# control-cluster-test.net
KiCad netlist of a schematic drawn in Altium Designer
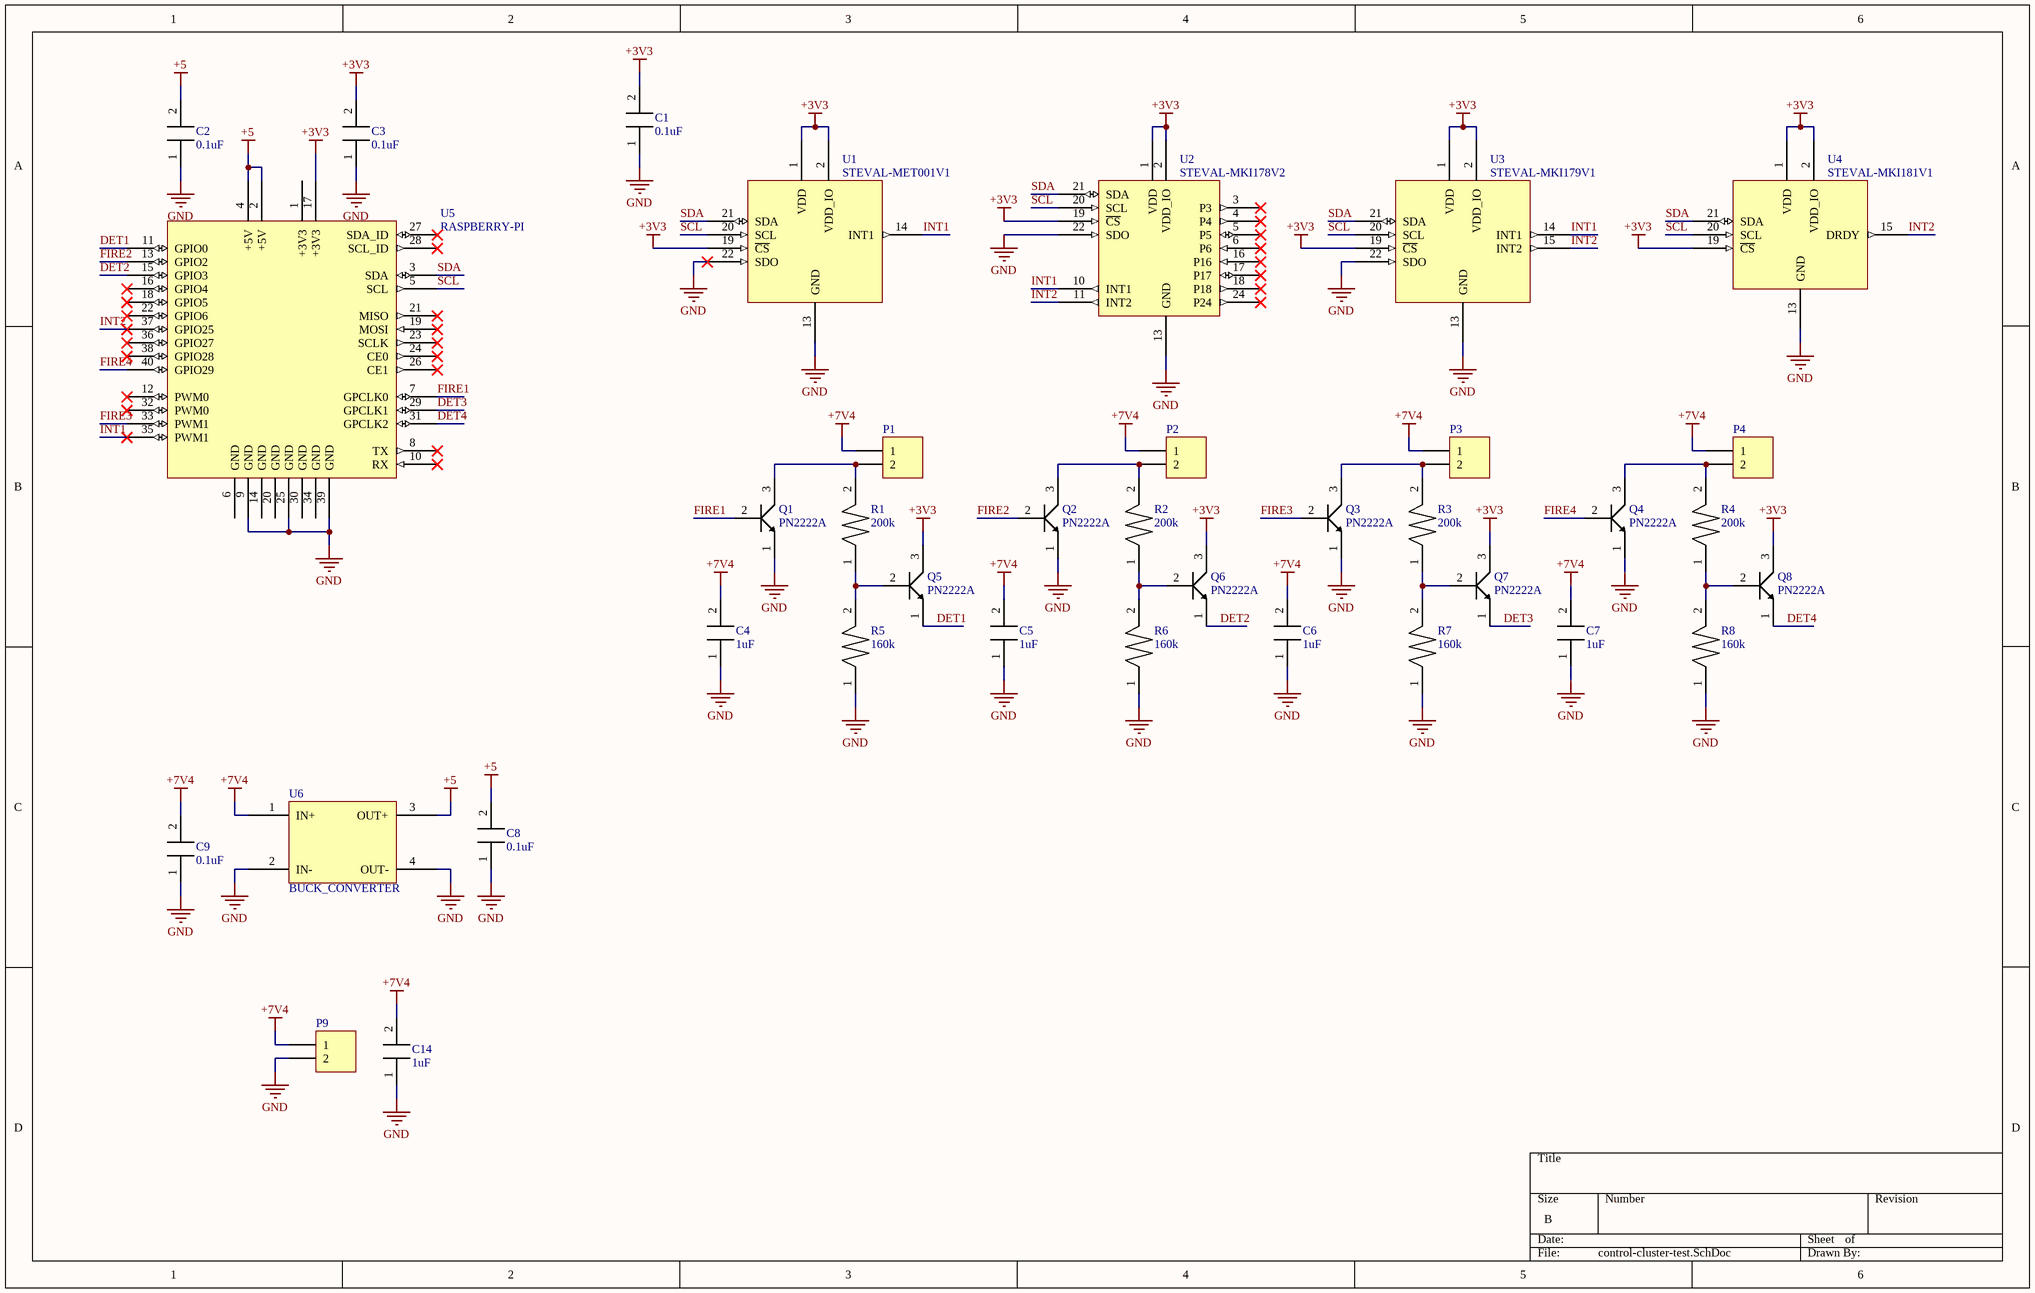
[diagram p0: control-cluster-test.SchDoc]

(export (version "E")
  (design (tool "Eeschema 10.0.6"))
  (components
    (comp (ref "C1")
      (value "0.1uF")
      (footprint "CAPACITOR")
      (libsource (lib "control-cluster-test") (part "CAPACITOR"))
    )
    (comp (ref "C2")
      (value "0.1uF")
      (footprint "CAPACITOR")
      (libsource (lib "control-cluster-test") (part "CAPACITOR"))
    )
    (comp (ref "C3")
      (value "0.1uF")
      (footprint "CAPACITOR")
      (libsource (lib "control-cluster-test") (part "CAPACITOR"))
    )
    (comp (ref "C4")
      (value "1uF")
      (footprint "CAPACITOR")
      (libsource (lib "control-cluster-test") (part "CAPACITOR"))
    )
    (comp (ref "C5")
      (value "1uF")
      (footprint "CAPACITOR")
      (libsource (lib "control-cluster-test") (part "CAPACITOR"))
    )
    (comp (ref "C6")
      (value "1uF")
      (footprint "CAPACITOR")
      (libsource (lib "control-cluster-test") (part "CAPACITOR"))
    )
    (comp (ref "C7")
      (value "1uF")
      (footprint "CAPACITOR")
      (libsource (lib "control-cluster-test") (part "CAPACITOR"))
    )
    (comp (ref "C8")
      (value "0.1uF")
      (footprint "CAPACITOR")
      (libsource (lib "control-cluster-test") (part "CAPACITOR"))
    )
    (comp (ref "C9")
      (value "0.1uF")
      (footprint "CAPACITOR")
      (libsource (lib "control-cluster-test") (part "CAPACITOR"))
    )
    (comp (ref "C14")
      (value "1uF")
      (footprint "CAPACITOR")
      (libsource (lib "control-cluster-test") (part "CAPACITOR"))
    )
    (comp (ref "P1")
      (value "Header 2")
      (footprint "HDR1X2")
      (description "Header, 2-Pin")
      (fields (field (name "PUBLISHER") "Altium Limited"))
      (libsource (lib "Miscellaneous Connectors") (part "Header 2"))
    )
    (comp (ref "P2")
      (value "Header 2")
      (footprint "HDR1X2")
      (description "Header, 2-Pin")
      (fields (field (name "PUBLISHER") "Altium Limited"))
      (libsource (lib "Miscellaneous Connectors") (part "Header 2"))
    )
    (comp (ref "P3")
      (value "Header 2")
      (footprint "HDR1X2")
      (description "Header, 2-Pin")
      (fields (field (name "PUBLISHER") "Altium Limited"))
      (libsource (lib "Miscellaneous Connectors") (part "Header 2"))
    )
    (comp (ref "P4")
      (value "Header 2")
      (footprint "HDR1X2")
      (description "Header, 2-Pin")
      (fields (field (name "PUBLISHER") "Altium Limited"))
      (libsource (lib "Miscellaneous Connectors") (part "Header 2"))
    )
    (comp (ref "P9")
      (value "Header 2")
      (footprint "HDR1X2")
      (description "Header, 2-Pin")
      (fields (field (name "PUBLISHER") "Altium Limited"))
      (libsource (lib "Miscellaneous Connectors") (part "Header 2"))
    )
    (comp (ref "Q1")
      (value "PN2222A")
      (footprint "PN2222A")
      (libsource (lib "control-cluster-test") (part "PN2222A"))
    )
    (comp (ref "Q2")
      (value "PN2222A")
      (footprint "PN2222A")
      (libsource (lib "control-cluster-test") (part "PN2222A"))
    )
    (comp (ref "Q3")
      (value "PN2222A")
      (footprint "PN2222A")
      (libsource (lib "control-cluster-test") (part "PN2222A"))
    )
    (comp (ref "Q4")
      (value "PN2222A")
      (footprint "PN2222A")
      (libsource (lib "control-cluster-test") (part "PN2222A"))
    )
    (comp (ref "Q5")
      (value "PN2222A")
      (footprint "PN2222A")
      (libsource (lib "control-cluster-test") (part "PN2222A"))
    )
    (comp (ref "Q6")
      (value "PN2222A")
      (footprint "PN2222A")
      (libsource (lib "control-cluster-test") (part "PN2222A"))
    )
    (comp (ref "Q7")
      (value "PN2222A")
      (footprint "PN2222A")
      (libsource (lib "control-cluster-test") (part "PN2222A"))
    )
    (comp (ref "Q8")
      (value "PN2222A")
      (footprint "PN2222A")
      (libsource (lib "control-cluster-test") (part "PN2222A"))
    )
    (comp (ref "R1")
      (value "200k")
      (footprint "RESISTOR")
      (libsource (lib "control-cluster-test") (part "RESISTOR"))
    )
    (comp (ref "R2")
      (value "200k")
      (footprint "RESISTOR")
      (libsource (lib "control-cluster-test") (part "RESISTOR"))
    )
    (comp (ref "R3")
      (value "200k")
      (footprint "RESISTOR")
      (libsource (lib "control-cluster-test") (part "RESISTOR"))
    )
    (comp (ref "R4")
      (value "200k")
      (footprint "RESISTOR")
      (libsource (lib "control-cluster-test") (part "RESISTOR"))
    )
    (comp (ref "R5")
      (value "160k")
      (footprint "RESISTOR")
      (libsource (lib "control-cluster-test") (part "RESISTOR"))
    )
    (comp (ref "R6")
      (value "160k")
      (footprint "RESISTOR")
      (libsource (lib "control-cluster-test") (part "RESISTOR"))
    )
    (comp (ref "R7")
      (value "160k")
      (footprint "RESISTOR")
      (libsource (lib "control-cluster-test") (part "RESISTOR"))
    )
    (comp (ref "R8")
      (value "160k")
      (footprint "RESISTOR")
      (libsource (lib "control-cluster-test") (part "RESISTOR"))
    )
    (comp (ref "U1")
      (value "STEVAL-MET001V1")
      (footprint "STEVAL")
      (libsource (lib "control-cluster-test") (part "STEVAL-MET001V1"))
    )
    (comp (ref "U2")
      (value "STEVAL-MKI178V2")
      (footprint "STEVAL")
      (libsource (lib "control-cluster-test") (part "STEVAL-MKI178V2"))
    )
    (comp (ref "U3")
      (value "STEVAL-MKI179V1")
      (footprint "STEVAL")
      (libsource (lib "control-cluster-test") (part "STEVAL-MKI179V1"))
    )
    (comp (ref "U4")
      (value "STEVAL-MKI181V1")
      (footprint "STEVAL")
      (libsource (lib "control-cluster-test") (part "STEVAL-MKI181V1"))
    )
    (comp (ref "U5")
      (value "RASPBERRY-PI")
      (footprint "RASPBERRY-PI")
      (libsource (lib "control-cluster-test") (part "RASPBERRY-PI"))
    )
    (comp (ref "U6")
      (value "BUCK_CONVERTER")
      (footprint "BUCK_CONVERTER")
      (libsource (lib "control-cluster-test") (part "BUCK_CONVERTER"))
    )
  )
  (nets
    (net (code "1") (name "+3V3") (class "Default")
      (node (ref "C1") (pin "2") (pinfunction "2_2") (pintype "passive"))
      (node (ref "C3") (pin "2") (pinfunction "2_2") (pintype "passive"))
      (node (ref "Q5") (pin "3") (pinfunction "C_3") (pintype "passive"))
      (node (ref "Q6") (pin "3") (pinfunction "C_3") (pintype "passive"))
      (node (ref "Q7") (pin "3") (pinfunction "C_3") (pintype "passive"))
      (node (ref "Q8") (pin "3") (pinfunction "C_3") (pintype "passive"))
      (node (ref "U1") (pin "1") (pinfunction "VDD_1") (pintype "power_in"))
      (node (ref "U1") (pin "19") (pinfunction "~{CS}_19") (pintype "input"))
      (node (ref "U1") (pin "2") (pinfunction "VDD_IO_2") (pintype "power_in"))
      (node (ref "U2") (pin "1") (pinfunction "VDD_1") (pintype "power_in"))
      (node (ref "U2") (pin "19") (pinfunction "~{CS}_19") (pintype "input"))
      (node (ref "U2") (pin "2") (pinfunction "VDD_IO_2") (pintype "power_in"))
      (node (ref "U3") (pin "1") (pinfunction "VDD_1") (pintype "power_in"))
      (node (ref "U3") (pin "19") (pinfunction "~{CS}_19") (pintype "input"))
      (node (ref "U3") (pin "2") (pinfunction "VDD_IO_2") (pintype "power_in"))
      (node (ref "U4") (pin "1") (pinfunction "VDD_1") (pintype "power_in"))
      (node (ref "U4") (pin "19") (pinfunction "~{CS}_19") (pintype "input"))
      (node (ref "U4") (pin "2") (pinfunction "VDD_IO_2") (pintype "power_in"))
      (node (ref "U5") (pin "17") (pinfunction "+3V3_17") (pintype "power_in"))
    )
    (net (code "2") (name "+5") (class "Default")
      (node (ref "C2") (pin "2") (pinfunction "2_2") (pintype "passive"))
      (node (ref "C8") (pin "2") (pinfunction "2_2") (pintype "passive"))
      (node (ref "U5") (pin "2") (pinfunction "+5V_2") (pintype "power_in"))
      (node (ref "U5") (pin "4") (pinfunction "+5V_4") (pintype "power_in"))
      (node (ref "U6") (pin "3") (pinfunction "OUT+_3") (pintype "passive"))
    )
    (net (code "3") (name "+7V4") (class "Default")
      (node (ref "C14") (pin "2") (pinfunction "2_2") (pintype "passive"))
      (node (ref "C4") (pin "2") (pinfunction "2_2") (pintype "passive"))
      (node (ref "C5") (pin "2") (pinfunction "2_2") (pintype "passive"))
      (node (ref "C6") (pin "2") (pinfunction "2_2") (pintype "passive"))
      (node (ref "C7") (pin "2") (pinfunction "2_2") (pintype "passive"))
      (node (ref "C9") (pin "2") (pinfunction "2_2") (pintype "passive"))
      (node (ref "P1") (pin "1") (pinfunction "1_1") (pintype "passive"))
      (node (ref "P2") (pin "1") (pinfunction "1_1") (pintype "passive"))
      (node (ref "P3") (pin "1") (pinfunction "1_1") (pintype "passive"))
      (node (ref "P4") (pin "1") (pinfunction "1_1") (pintype "passive"))
      (node (ref "P9") (pin "1") (pinfunction "1_1") (pintype "passive"))
      (node (ref "U6") (pin "1") (pinfunction "IN+_1") (pintype "passive"))
    )
    (net (code "4") (name "/DET1") (class "Default")
      (node (ref "Q5") (pin "1") (pinfunction "E_1") (pintype "passive"))
      (node (ref "U5") (pin "11") (pinfunction "GPIO0_11") (pintype "bidirectional"))
    )
    (net (code "5") (name "/DET2") (class "Default")
      (node (ref "Q6") (pin "1") (pinfunction "E_1") (pintype "passive"))
      (node (ref "U5") (pin "15") (pinfunction "GPIO3_15") (pintype "bidirectional"))
    )
    (net (code "6") (name "/DET3") (class "Default")
      (node (ref "Q7") (pin "1") (pinfunction "E_1") (pintype "passive"))
      (node (ref "U5") (pin "29") (pinfunction "GPCLK1_29") (pintype "bidirectional"))
    )
    (net (code "7") (name "/DET4") (class "Default")
      (node (ref "Q8") (pin "1") (pinfunction "E_1") (pintype "passive"))
      (node (ref "U5") (pin "31") (pinfunction "GPCLK2_31") (pintype "bidirectional"))
    )
    (net (code "8") (name "/FIRE1") (class "Default")
      (node (ref "Q1") (pin "2") (pinfunction "B_2") (pintype "passive"))
      (node (ref "U5") (pin "7") (pinfunction "GPCLK0_7") (pintype "bidirectional"))
    )
    (net (code "9") (name "/FIRE2") (class "Default")
      (node (ref "Q2") (pin "2") (pinfunction "B_2") (pintype "passive"))
      (node (ref "U5") (pin "13") (pinfunction "GPIO2_13") (pintype "bidirectional"))
    )
    (net (code "10") (name "/FIRE3") (class "Default")
      (node (ref "Q3") (pin "2") (pinfunction "B_2") (pintype "passive"))
      (node (ref "U5") (pin "33") (pinfunction "PWM1_33") (pintype "bidirectional"))
    )
    (net (code "11") (name "/FIRE4") (class "Default")
      (node (ref "Q4") (pin "2") (pinfunction "B_2") (pintype "passive"))
      (node (ref "U5") (pin "40") (pinfunction "GPIO29_40") (pintype "bidirectional"))
    )
    (net (code "12") (name "/INT1") (class "Default")
      (node (ref "U1") (pin "14") (pinfunction "INT1_14") (pintype "output"))
      (node (ref "U2") (pin "10") (pinfunction "INT1_10") (pintype "output"))
      (node (ref "U3") (pin "14") (pinfunction "INT1_14") (pintype "output"))
      (node (ref "U5") (pin "35") (pinfunction "PWM1_35") (pintype "bidirectional"))
    )
    (net (code "13") (name "/INT2") (class "Default")
      (node (ref "U2") (pin "11") (pinfunction "INT2_11") (pintype "output"))
      (node (ref "U3") (pin "15") (pinfunction "INT2_15") (pintype "output"))
      (node (ref "U4") (pin "15") (pinfunction "DRDY_15") (pintype "output"))
      (node (ref "U5") (pin "37") (pinfunction "GPIO25_37") (pintype "bidirectional"))
    )
    (net (code "14") (name "/SCL") (class "Default")
      (node (ref "U1") (pin "20") (pinfunction "SCL_20") (pintype "input"))
      (node (ref "U2") (pin "20") (pinfunction "SCL_20") (pintype "input"))
      (node (ref "U3") (pin "20") (pinfunction "SCL_20") (pintype "input"))
      (node (ref "U4") (pin "20") (pinfunction "SCL_20") (pintype "input"))
      (node (ref "U5") (pin "5") (pinfunction "SCL_5") (pintype "output"))
    )
    (net (code "15") (name "/SDA") (class "Default")
      (node (ref "U1") (pin "21") (pinfunction "SDA_21") (pintype "bidirectional"))
      (node (ref "U2") (pin "21") (pinfunction "SDA_21") (pintype "bidirectional"))
      (node (ref "U3") (pin "21") (pinfunction "SDA_21") (pintype "bidirectional"))
      (node (ref "U4") (pin "21") (pinfunction "SDA_21") (pintype "bidirectional"))
      (node (ref "U5") (pin "3") (pinfunction "SDA_3") (pintype "bidirectional"))
    )
    (net (code "16") (name "GND") (class "Default")
      (node (ref "C1") (pin "1") (pinfunction "1_1") (pintype "passive"))
      (node (ref "C14") (pin "1") (pinfunction "1_1") (pintype "passive"))
      (node (ref "C2") (pin "1") (pinfunction "1_1") (pintype "passive"))
      (node (ref "C3") (pin "1") (pinfunction "1_1") (pintype "passive"))
      (node (ref "C4") (pin "1") (pinfunction "1_1") (pintype "passive"))
      (node (ref "C5") (pin "1") (pinfunction "1_1") (pintype "passive"))
      (node (ref "C6") (pin "1") (pinfunction "1_1") (pintype "passive"))
      (node (ref "C7") (pin "1") (pinfunction "1_1") (pintype "passive"))
      (node (ref "C8") (pin "1") (pinfunction "1_1") (pintype "passive"))
      (node (ref "C9") (pin "1") (pinfunction "1_1") (pintype "passive"))
      (node (ref "P9") (pin "2") (pinfunction "2_2") (pintype "passive"))
      (node (ref "Q1") (pin "1") (pinfunction "E_1") (pintype "passive"))
      (node (ref "Q2") (pin "1") (pinfunction "E_1") (pintype "passive"))
      (node (ref "Q3") (pin "1") (pinfunction "E_1") (pintype "passive"))
      (node (ref "Q4") (pin "1") (pinfunction "E_1") (pintype "passive"))
      (node (ref "R5") (pin "1") (pinfunction "1_1") (pintype "passive"))
      (node (ref "R6") (pin "1") (pinfunction "1_1") (pintype "passive"))
      (node (ref "R7") (pin "1") (pinfunction "1_1") (pintype "passive"))
      (node (ref "R8") (pin "1") (pinfunction "1_1") (pintype "passive"))
      (node (ref "U1") (pin "13") (pinfunction "GND_13") (pintype "passive"))
      (node (ref "U1") (pin "22") (pinfunction "SDO_22") (pintype "input"))
      (node (ref "U2") (pin "13") (pinfunction "GND_13") (pintype "passive"))
      (node (ref "U2") (pin "22") (pinfunction "SDO_22") (pintype "input"))
      (node (ref "U3") (pin "13") (pinfunction "GND_13") (pintype "passive"))
      (node (ref "U3") (pin "22") (pinfunction "SDO_22") (pintype "input"))
      (node (ref "U4") (pin "13") (pinfunction "GND_13") (pintype "passive"))
      (node (ref "U5") (pin "25") (pinfunction "GND_25") (pintype "passive"))
      (node (ref "U5") (pin "39") (pinfunction "GND_39") (pintype "passive"))
      (node (ref "U5") (pin "9") (pinfunction "GND_9") (pintype "passive"))
      (node (ref "U6") (pin "2") (pinfunction "IN-_2") (pintype "passive"))
      (node (ref "U6") (pin "4") (pinfunction "OUT-_4") (pintype "passive"))
    )
    (net (code "17") (name "Net-(Q1-C)") (class "Default")
      (node (ref "P1") (pin "2") (pinfunction "2_2") (pintype "passive"))
      (node (ref "Q1") (pin "3") (pinfunction "C_3") (pintype "passive"))
      (node (ref "R1") (pin "2") (pinfunction "2_2") (pintype "passive"))
    )
    (net (code "18") (name "Net-(Q2-C)") (class "Default")
      (node (ref "P2") (pin "2") (pinfunction "2_2") (pintype "passive"))
      (node (ref "Q2") (pin "3") (pinfunction "C_3") (pintype "passive"))
      (node (ref "R2") (pin "2") (pinfunction "2_2") (pintype "passive"))
    )
    (net (code "19") (name "Net-(Q3-C)") (class "Default")
      (node (ref "P3") (pin "2") (pinfunction "2_2") (pintype "passive"))
      (node (ref "Q3") (pin "3") (pinfunction "C_3") (pintype "passive"))
      (node (ref "R3") (pin "2") (pinfunction "2_2") (pintype "passive"))
    )
    (net (code "20") (name "Net-(Q4-C)") (class "Default")
      (node (ref "P4") (pin "2") (pinfunction "2_2") (pintype "passive"))
      (node (ref "Q4") (pin "3") (pinfunction "C_3") (pintype "passive"))
      (node (ref "R4") (pin "2") (pinfunction "2_2") (pintype "passive"))
    )
    (net (code "21") (name "Net-(Q5-B)") (class "Default")
      (node (ref "Q5") (pin "2") (pinfunction "B_2") (pintype "passive"))
      (node (ref "R1") (pin "1") (pinfunction "1_1") (pintype "passive"))
      (node (ref "R5") (pin "2") (pinfunction "2_2") (pintype "passive"))
    )
    (net (code "22") (name "Net-(Q6-B)") (class "Default")
      (node (ref "Q6") (pin "2") (pinfunction "B_2") (pintype "passive"))
      (node (ref "R2") (pin "1") (pinfunction "1_1") (pintype "passive"))
      (node (ref "R6") (pin "2") (pinfunction "2_2") (pintype "passive"))
    )
    (net (code "23") (name "Net-(Q7-B)") (class "Default")
      (node (ref "Q7") (pin "2") (pinfunction "B_2") (pintype "passive"))
      (node (ref "R3") (pin "1") (pinfunction "1_1") (pintype "passive"))
      (node (ref "R7") (pin "2") (pinfunction "2_2") (pintype "passive"))
    )
    (net (code "24") (name "Net-(Q8-B)") (class "Default")
      (node (ref "Q8") (pin "2") (pinfunction "B_2") (pintype "passive"))
      (node (ref "R4") (pin "1") (pinfunction "1_1") (pintype "passive"))
      (node (ref "R8") (pin "2") (pinfunction "2_2") (pintype "passive"))
    )
    (net (code "25") (name "unconnected-(U2-P3-Pad3)") (class "Default")
      (node (ref "U2") (pin "3") (pinfunction "P3_3") (pintype "output+no_connect"))
    )
    (net (code "26") (name "unconnected-(U2-P4-Pad4)") (class "Default")
      (node (ref "U2") (pin "4") (pinfunction "P4_4") (pintype "output+no_connect"))
    )
    (net (code "27") (name "unconnected-(U2-P5-Pad5)") (class "Default")
      (node (ref "U2") (pin "5") (pinfunction "P5_5") (pintype "bidirectional+no_connect"))
    )
    (net (code "28") (name "unconnected-(U2-P6-Pad6)") (class "Default")
      (node (ref "U2") (pin "6") (pinfunction "P6_6") (pintype "input+no_connect"))
    )
    (net (code "29") (name "unconnected-(U2-P16-Pad16)") (class "Default")
      (node (ref "U2") (pin "16") (pinfunction "P16_16") (pintype "input+no_connect"))
    )
    (net (code "30") (name "unconnected-(U2-P17-Pad17)") (class "Default")
      (node (ref "U2") (pin "17") (pinfunction "P17_17") (pintype "bidirectional+no_connect"))
    )
    (net (code "31") (name "unconnected-(U2-P18-Pad18)") (class "Default")
      (node (ref "U2") (pin "18") (pinfunction "P18_18") (pintype "output+no_connect"))
    )
    (net (code "32") (name "unconnected-(U2-P24-Pad24)") (class "Default")
      (node (ref "U2") (pin "24") (pinfunction "P24_24") (pintype "output+no_connect"))
    )
    (net (code "33") (name "unconnected-(U5-+3V3-Pad1)") (class "Default")
      (node (ref "U5") (pin "1") (pinfunction "+3V3_1") (pintype "power_in"))
    )
    (net (code "34") (name "unconnected-(U5-CE0-Pad24)") (class "Default")
      (node (ref "U5") (pin "24") (pinfunction "CE0_24") (pintype "output+no_connect"))
    )
    (net (code "35") (name "unconnected-(U5-CE1-Pad26)") (class "Default")
      (node (ref "U5") (pin "26") (pinfunction "CE1_26") (pintype "output+no_connect"))
    )
    (net (code "36") (name "unconnected-(U5-GND-Pad6)") (class "Default")
      (node (ref "U5") (pin "6") (pinfunction "GND_6") (pintype "passive"))
    )
    (net (code "37") (name "unconnected-(U5-GND-Pad14)") (class "Default")
      (node (ref "U5") (pin "14") (pinfunction "GND_14") (pintype "passive"))
    )
    (net (code "38") (name "unconnected-(U5-GND-Pad20)") (class "Default")
      (node (ref "U5") (pin "20") (pinfunction "GND_20") (pintype "passive"))
    )
    (net (code "39") (name "unconnected-(U5-GND-Pad30)") (class "Default")
      (node (ref "U5") (pin "30") (pinfunction "GND_30") (pintype "passive"))
    )
    (net (code "40") (name "unconnected-(U5-GND-Pad34)") (class "Default")
      (node (ref "U5") (pin "34") (pinfunction "GND_34") (pintype "passive"))
    )
    (net (code "41") (name "unconnected-(U5-GPIO4-Pad16)") (class "Default")
      (node (ref "U5") (pin "16") (pinfunction "GPIO4_16") (pintype "bidirectional+no_connect"))
    )
    (net (code "42") (name "unconnected-(U5-GPIO5-Pad18)") (class "Default")
      (node (ref "U5") (pin "18") (pinfunction "GPIO5_18") (pintype "bidirectional+no_connect"))
    )
    (net (code "43") (name "unconnected-(U5-GPIO6-Pad22)") (class "Default")
      (node (ref "U5") (pin "22") (pinfunction "GPIO6_22") (pintype "bidirectional+no_connect"))
    )
    (net (code "44") (name "unconnected-(U5-GPIO27-Pad36)") (class "Default")
      (node (ref "U5") (pin "36") (pinfunction "GPIO27_36") (pintype "bidirectional+no_connect"))
    )
    (net (code "45") (name "unconnected-(U5-GPIO28-Pad38)") (class "Default")
      (node (ref "U5") (pin "38") (pinfunction "GPIO28_38") (pintype "bidirectional+no_connect"))
    )
    (net (code "46") (name "unconnected-(U5-MISO-Pad21)") (class "Default")
      (node (ref "U5") (pin "21") (pinfunction "MISO_21") (pintype "output+no_connect"))
    )
    (net (code "47") (name "unconnected-(U5-MOSI-Pad19)") (class "Default")
      (node (ref "U5") (pin "19") (pinfunction "MOSI_19") (pintype "input+no_connect"))
    )
    (net (code "48") (name "unconnected-(U5-PWM0-Pad12)") (class "Default")
      (node (ref "U5") (pin "12") (pinfunction "PWM0_12") (pintype "bidirectional+no_connect"))
    )
    (net (code "49") (name "unconnected-(U5-PWM0-Pad32)") (class "Default")
      (node (ref "U5") (pin "32") (pinfunction "PWM0_32") (pintype "bidirectional+no_connect"))
    )
    (net (code "50") (name "unconnected-(U5-RX-Pad10)") (class "Default")
      (node (ref "U5") (pin "10") (pinfunction "RX_10") (pintype "input+no_connect"))
    )
    (net (code "51") (name "unconnected-(U5-SCLK-Pad23)") (class "Default")
      (node (ref "U5") (pin "23") (pinfunction "SCLK_23") (pintype "output+no_connect"))
    )
    (net (code "52") (name "unconnected-(U5-SCL_ID-Pad28)") (class "Default")
      (node (ref "U5") (pin "28") (pinfunction "SCL_ID_28") (pintype "output+no_connect"))
    )
    (net (code "53") (name "unconnected-(U5-SDA_ID-Pad27)") (class "Default")
      (node (ref "U5") (pin "27") (pinfunction "SDA_ID_27") (pintype "bidirectional+no_connect"))
    )
    (net (code "54") (name "unconnected-(U5-TX-Pad8)") (class "Default")
      (node (ref "U5") (pin "8") (pinfunction "TX_8") (pintype "output+no_connect"))
    )
  )
)
